# pixie_bottle_mrk2.net
KiCad netlist of a schematic drawn in EAGLE
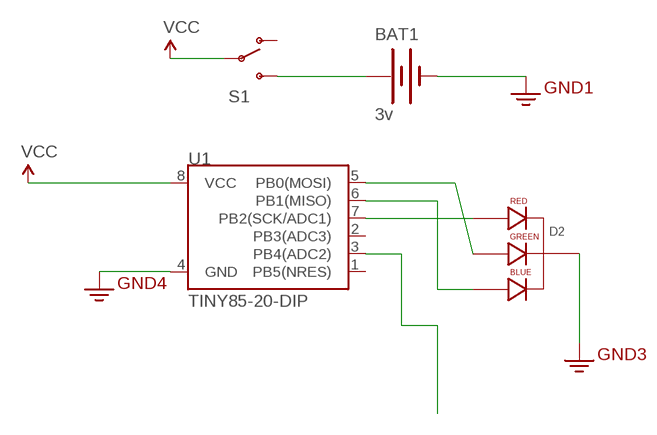
[diagram p0: schematic, sheet 1]

(export (version "E")
  (design (tool "Eeschema 10.0.6"))
  (components
    (comp (ref "BAT1")
      (value "3v")
      (footprint "eagle-import:BATTCOM_20MM_PTH")
      (libsource (lib "eagle-import") (part "BATTERY20PTH"))
    )
    (comp (ref "D2")
      (value "LED-RGB-CC-THRUDIFFUSE")
      (footprint "eagle-import:LED-RGB-THRU")
      (libsource (lib "eagle-import") (part "LED-RGB-CC-THRUDIFFUSE"))
    )
    (comp (ref "S1")
      (value "SWITCH-SPDTPTH")
      (footprint "eagle-import:SWITCH-SPDT")
      (libsource (lib "eagle-import") (part "SWITCH-SPDTPTH"))
    )
    (comp (ref "U1")
      (value "TINY85-20-DIP")
      (footprint "eagle-import:DIP08")
      (libsource (lib "eagle-import") (part "ATTINY45TINY85-20-DIP"))
    )
  )
  (nets
    (net (code "1") (name "GND2") (class "Default")
      (node (ref "BAT1") (pin "2") (pinfunction "-_2") (pintype "power_in"))
      (node (ref "D2") (pin "2") (pinfunction "CATHODE_2") (pintype "bidirectional"))
      (node (ref "U1") (pin "4") (pinfunction "GND_4") (pintype "bidirectional"))
    )
    (net (code "2") (name "Net-(BAT1-+)") (class "Default")
      (node (ref "BAT1") (pin "1") (pinfunction "+_1") (pintype "power_in"))
      (node (ref "S1") (pin "3") (pinfunction "S_3") (pintype "passive"))
    )
    (net (code "3") (name "Net-(D2-BLUE_CATHODE)") (class "Default")
      (node (ref "D2") (pin "4") (pinfunction "BLUE_CATHODE_4") (pintype "bidirectional"))
      (node (ref "U1") (pin "6") (pinfunction "PB1(MISO)_6") (pintype "bidirectional"))
    )
    (net (code "4") (name "Net-(D2-GREEN_CATHODE)") (class "Default")
      (node (ref "D2") (pin "3") (pinfunction "GREEN_CATHODE_3") (pintype "bidirectional"))
      (node (ref "U1") (pin "5") (pinfunction "PB0(MOSI)_5") (pintype "bidirectional"))
    )
    (net (code "5") (name "Net-(D2-RED_CATHODE)") (class "Default")
      (node (ref "D2") (pin "1") (pinfunction "RED_CATHODE_1") (pintype "bidirectional"))
      (node (ref "U1") (pin "7") (pinfunction "PB2(SCK/ADC1)_7") (pintype "bidirectional"))
    )
    (net (code "6") (name "VCC") (class "Default")
      (node (ref "S1") (pin "2") (pinfunction "P_2") (pintype "passive"))
      (node (ref "U1") (pin "8") (pinfunction "VCC_8") (pintype "bidirectional"))
    )
    (net (code "7") (name "unconnected-(S1-O-Pad1)") (class "Default")
      (node (ref "S1") (pin "1") (pinfunction "O_1") (pintype "passive"))
    )
    (net (code "8") (name "unconnected-(U1-PB3(ADC3)-Pad2)") (class "Default")
      (node (ref "U1") (pin "2") (pinfunction "PB3(ADC3)_2") (pintype "bidirectional"))
    )
    (net (code "9") (name "unconnected-(U1-PB4(ADC2)-Pad3)") (class "Default")
      (node (ref "U1") (pin "3") (pinfunction "PB4(ADC2)_3") (pintype "bidirectional"))
    )
    (net (code "10") (name "unconnected-(U1-PB5(NRES)-Pad1)") (class "Default")
      (node (ref "U1") (pin "1") (pinfunction "PB5(NRES)_1") (pintype "bidirectional"))
    )
  )
)
